# lpc11c14.net
KiCad netlist of a schematic drawn in Altium Designer
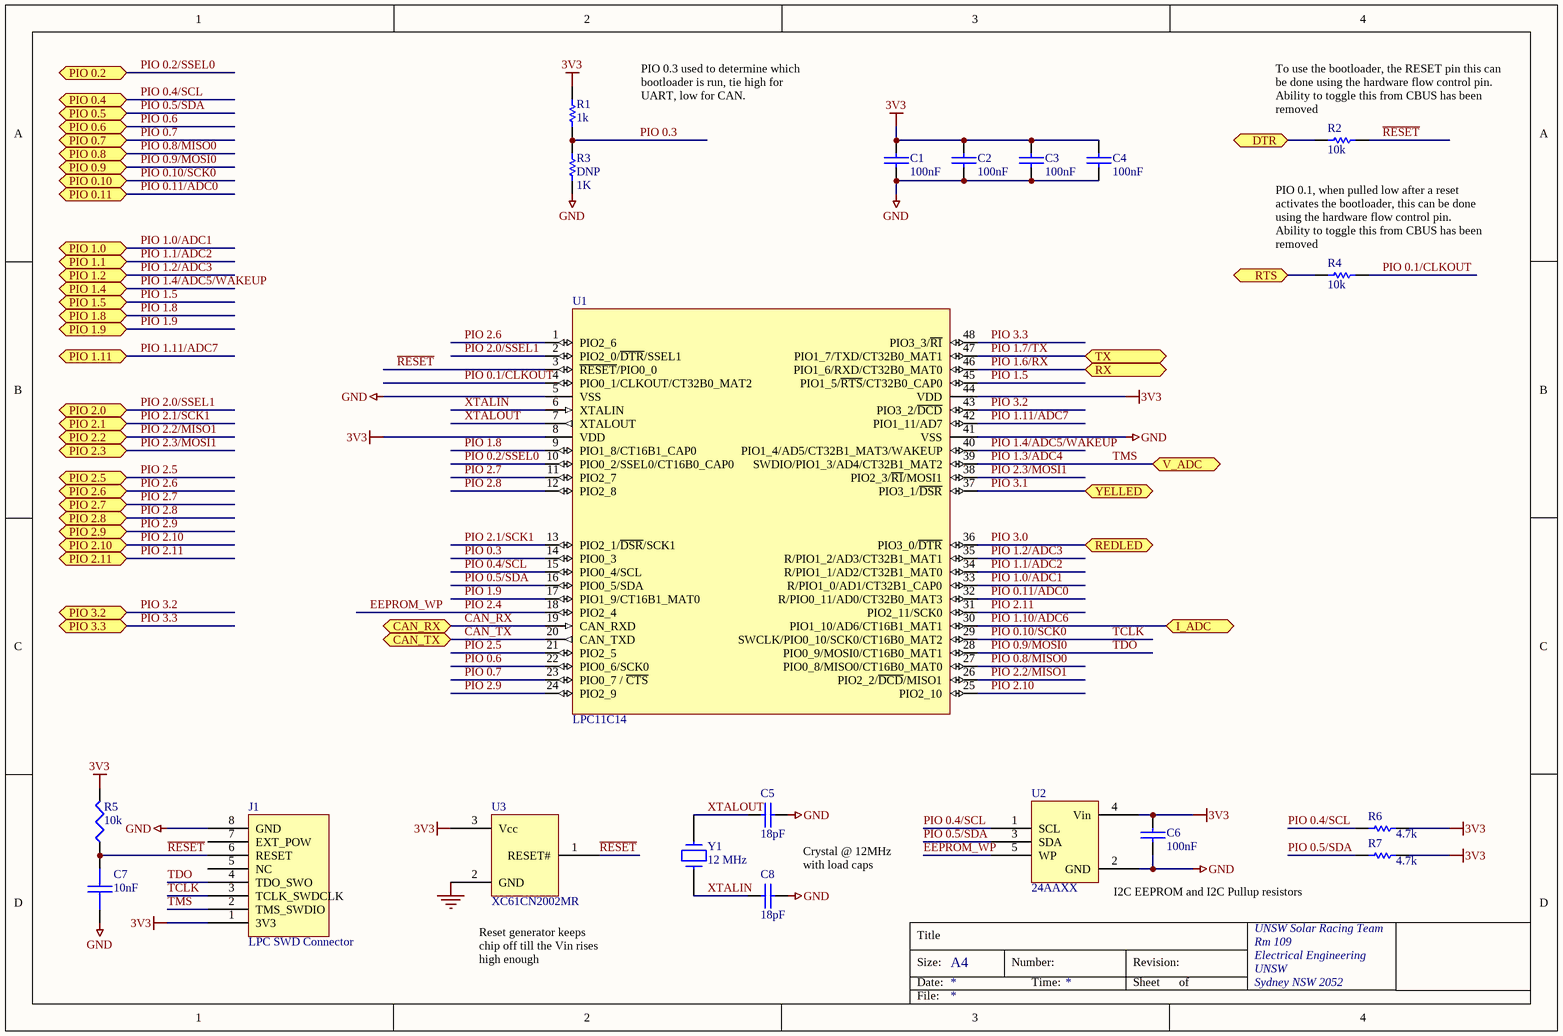
[diagram p0: lpc11c14.SchDoc]

(export (version "E")
  (design (tool "Eeschema 10.0.6"))
  (components
    (comp (ref "C1")
      (value "100nF")
      (footprint "0603")
      (description "Capacitor")
      (libsource (lib "*") (part "CAP"))
    )
    (comp (ref "C2")
      (value "100nF")
      (footprint "0603")
      (description "Capacitor")
      (libsource (lib "*") (part "CAP"))
    )
    (comp (ref "C3")
      (value "100nF")
      (footprint "0603")
      (description "Capacitor")
      (libsource (lib "*") (part "CAP"))
    )
    (comp (ref "C4")
      (value "100nF")
      (footprint "0603")
      (description "Capacitor")
      (libsource (lib "*") (part "CAP"))
    )
    (comp (ref "C5")
      (value "18pF")
      (footprint "0603")
      (description "Capacitor")
      (fields
        (field (name "MANUFACTURER") "Kemet")
        (field (name "MANUFACTURER PART NUMBER") "CBR06C180FAGAC")
      )
      (libsource (lib "*") (part "CAP"))
    )
    (comp (ref "C6")
      (value "100nF")
      (footprint "0603")
      (description "Capacitor")
      (libsource (lib "*") (part "CAP"))
    )
    (comp (ref "C7")
      (value "10nF")
      (footprint "0603")
      (description "Capacitor")
      (libsource (lib "SunswiftLib20030312RR") (part "CAP"))
    )
    (comp (ref "C8")
      (value "18pF")
      (footprint "0603")
      (description "Capacitor")
      (fields
        (field (name "MANUFACTURER") "Kemet")
        (field (name "MANUFACTURER PART NUMBER") "CBR06C180FAGAC")
      )
      (libsource (lib "*") (part "CAP"))
    )
    (comp (ref "J1")
      (value "LPC SWD Connector")
      (footprint "IDC8")
      (libsource (lib "2009_BatteryMaster") (part "LPCLink_Connector"))
    )
    (comp (ref "R1")
      (value "1k")
      (footprint "0603")
      (description "Semiconductor Resistor")
      (fields (field (name "PUBLISHER") "Altium Limited"))
      (libsource (lib "Miscellaneous Devices") (part "Res Semi"))
    )
    (comp (ref "R2")
      (value "10k")
      (footprint "0603")
      (description "Semiconductor Resistor")
      (fields (field (name "PUBLISHER") "Altium Limited"))
      (libsource (lib "Miscellaneous Devices") (part "Res Semi"))
    )
    (comp (ref "R3")
      (value "DNP")
      (footprint "0603")
      (description "Semiconductor Resistor")
      (fields (field (name "ALTIUM_VALUE") "1K") (field (name "PUBLISHER") "Altium Limited"))
      (libsource (lib "Miscellaneous Devices") (part "Res Semi"))
    )
    (comp (ref "R4")
      (value "10k")
      (footprint "0603")
      (description "Semiconductor Resistor")
      (fields (field (name "PUBLISHER") "Altium Limited"))
      (libsource (lib "Miscellaneous Devices") (part "Res Semi"))
    )
    (comp (ref "R5")
      (value "10k")
      (footprint "0603")
      (description "Resistor")
      (libsource (lib "SunswiftLib20030312RR") (part "RES1"))
    )
    (comp (ref "R6")
      (value "4.7k")
      (footprint "0603")
      (description "Semiconductor Resistor")
      (fields (field (name "PUBLISHER") "Altium Limited"))
      (libsource (lib "Miscellaneous Devices") (part "Res Semi"))
    )
    (comp (ref "R7")
      (value "4.7k")
      (footprint "0603")
      (description "Semiconductor Resistor")
      (fields (field (name "PUBLISHER") "Altium Limited"))
      (libsource (lib "Miscellaneous Devices") (part "Res Semi"))
    )
    (comp (ref "U1")
      (value "LPC11C14")
      (footprint "QFP48")
      (description "NXP LPC11C14 Microcontroller")
      (libsource (lib "LPC") (part "LPC11C14_Full"))
    )
    (comp (ref "U2")
      (value "24AAXX")
      (footprint "SOT23-5")
      (description "I2C EEPROM for SOT23-5 package")
      (libsource (lib "MiscellaneousIC") (part "24AAXX"))
    )
    (comp (ref "U3")
      (value "XC61CN2002MR")
      (footprint "SOT23-3")
      (description "SOT23 reset generator")
      (libsource (lib "*") (part "XC61F"))
    )
    (comp (ref "Y1")
      (value "12 MHz")
      (footprint "HC49/4H")
      (description "Crystal")
      (libsource (lib "*") (part "CRYSTAL"))
    )
  )
  (nets
    (net (code "1") (name "/CAN_RX") (class "Default")
      (node (ref "U1") (pin "19") (pinfunction "CAN_RXD_19") (pintype "input"))
    )
    (net (code "2") (name "/CAN_TX") (class "Default")
      (node (ref "U1") (pin "20") (pinfunction "CAN_TXD_20") (pintype "output"))
    )
    (net (code "3") (name "/DTR") (class "Default")
      (node (ref "R2") (pin "1") (pinfunction "1_1") (pintype "passive"))
    )
    (net (code "4") (name "/EEPROM_WP") (class "Default")
      (node (ref "U1") (pin "18") (pinfunction "PIO2_4_18") (pintype "bidirectional"))
      (node (ref "U2") (pin "5") (pinfunction "WP_5") (pintype "passive"))
    )
    (net (code "5") (name "/PIO 0.1{slash}CLKOUT") (class "Default")
      (node (ref "R4") (pin "2") (pinfunction "2_2") (pintype "passive"))
      (node (ref "U1") (pin "4") (pinfunction "PIO0_1/CLKOUT/CT32B0_MAT2_4") (pintype "bidirectional"))
    )
    (net (code "6") (name "/PIO 0.2{slash}SSEL0") (class "Default")
      (node (ref "U1") (pin "10") (pinfunction "PIO0_2/SSEL0/CT16B0_CAP0_10") (pintype "bidirectional"))
    )
    (net (code "7") (name "/PIO 0.3") (class "Default")
      (node (ref "R1") (pin "1") (pinfunction "1_1") (pintype "passive"))
      (node (ref "R3") (pin "2") (pinfunction "2_2") (pintype "passive"))
      (node (ref "U1") (pin "14") (pinfunction "PIO0_3_14") (pintype "bidirectional"))
    )
    (net (code "8") (name "/PIO 0.4{slash}SCL") (class "Default")
      (node (ref "R6") (pin "1") (pinfunction "1_1") (pintype "passive"))
      (node (ref "U1") (pin "15") (pinfunction "PIO0_4/SCL_15") (pintype "bidirectional"))
      (node (ref "U2") (pin "1") (pinfunction "SCL_1") (pintype "passive"))
    )
    (net (code "9") (name "/PIO 0.5{slash}SDA") (class "Default")
      (node (ref "R7") (pin "1") (pinfunction "1_1") (pintype "passive"))
      (node (ref "U1") (pin "16") (pinfunction "PIO0_5/SDA_16") (pintype "bidirectional"))
      (node (ref "U2") (pin "3") (pinfunction "SDA_3") (pintype "passive"))
    )
    (net (code "10") (name "/PIO 0.6") (class "Default")
      (node (ref "U1") (pin "22") (pinfunction "PIO0_6/SCK0_22") (pintype "bidirectional"))
    )
    (net (code "11") (name "/PIO 0.7") (class "Default")
      (node (ref "U1") (pin "23") (pinfunction "PIO0_7_/_~{CTS}_23") (pintype "bidirectional"))
    )
    (net (code "12") (name "/PIO 0.8{slash}MISO0") (class "Default")
      (node (ref "U1") (pin "27") (pinfunction "PIO0_8/MISO0/CT16B0_MAT0_27") (pintype "bidirectional"))
    )
    (net (code "13") (name "/PIO 0.9{slash}MOSI0") (class "Default")
      (node (ref "J1") (pin "4") (pinfunction "TDO_SWO_4") (pintype "passive"))
      (node (ref "U1") (pin "28") (pinfunction "PIO0_9/MOSI0/CT16B0_MAT1_28") (pintype "bidirectional"))
    )
    (net (code "14") (name "/PIO 0.10{slash}SCK0") (class "Default")
      (node (ref "J1") (pin "3") (pinfunction "TCLK_SWDCLK_3") (pintype "passive"))
      (node (ref "U1") (pin "29") (pinfunction "SWCLK/PIO0_10/SCK0/CT16B0_MAT2_29") (pintype "bidirectional"))
    )
    (net (code "15") (name "/PIO 0.11{slash}ADC0") (class "Default")
      (node (ref "U1") (pin "32") (pinfunction "R/PIO0_11/AD0/CT32B0_MAT3_32") (pintype "bidirectional"))
    )
    (net (code "16") (name "/PIO 1.0{slash}ADC1") (class "Default")
      (node (ref "U1") (pin "33") (pinfunction "R/PIO1_0/AD1/CT32B1_CAP0_33") (pintype "bidirectional"))
    )
    (net (code "17") (name "/PIO 1.1{slash}ADC2") (class "Default")
      (node (ref "U1") (pin "34") (pinfunction "R/PIO1_1/AD2/CT32B1_MAT0_34") (pintype "bidirectional"))
    )
    (net (code "18") (name "/PIO 1.2{slash}ADC3") (class "Default")
      (node (ref "U1") (pin "35") (pinfunction "R/PIO1_2/AD3/CT32B1_MAT1_35") (pintype "bidirectional"))
    )
    (net (code "19") (name "/PIO 1.3{slash}ADC4") (class "Default")
      (node (ref "J1") (pin "2") (pinfunction "TMS_SWDIO_2") (pintype "passive"))
      (node (ref "U1") (pin "39") (pinfunction "SWDIO/PIO1_3/AD4/CT32B1_MAT2_39") (pintype "bidirectional"))
    )
    (net (code "20") (name "/PIO 1.4{slash}ADC5{slash}WAKEUP") (class "Default")
      (node (ref "U1") (pin "40") (pinfunction "PIO1_4/AD5/CT32B1_MAT3/WAKEUP_40") (pintype "bidirectional"))
    )
    (net (code "21") (name "/PIO 1.5") (class "Default")
      (node (ref "U1") (pin "45") (pinfunction "PIO1_5/~{RTS}/CT32B0_CAP0_45") (pintype "bidirectional"))
    )
    (net (code "22") (name "/PIO 1.6{slash}RX") (class "Default")
      (node (ref "U1") (pin "46") (pinfunction "PIO1_6/RXD/CT32B0_MAT0_46") (pintype "bidirectional"))
    )
    (net (code "23") (name "/PIO 1.7{slash}TX") (class "Default")
      (node (ref "U1") (pin "47") (pinfunction "PIO1_7/TXD/CT32B0_MAT1_47") (pintype "bidirectional"))
    )
    (net (code "24") (name "/PIO 1.8") (class "Default")
      (node (ref "U1") (pin "9") (pinfunction "PIO1_8/CT16B1_CAP0_9") (pintype "bidirectional"))
    )
    (net (code "25") (name "/PIO 1.9") (class "Default")
      (node (ref "U1") (pin "17") (pinfunction "PIO1_9/CT16B1_MAT0_17") (pintype "bidirectional"))
    )
    (net (code "26") (name "/PIO 1.10{slash}ADC6") (class "Default")
      (node (ref "U1") (pin "30") (pinfunction "PIO1_10/AD6/CT16B1_MAT1_30") (pintype "bidirectional"))
    )
    (net (code "27") (name "/PIO 1.11{slash}ADC7") (class "Default")
      (node (ref "U1") (pin "42") (pinfunction "PIO1_11/AD7_42") (pintype "bidirectional"))
    )
    (net (code "28") (name "/PIO 2.0{slash}SSEL1") (class "Default")
      (node (ref "U1") (pin "2") (pinfunction "PIO2_0/~{DTR}/SSEL1_2") (pintype "bidirectional"))
    )
    (net (code "29") (name "/PIO 2.1{slash}SCK1") (class "Default")
      (node (ref "U1") (pin "13") (pinfunction "PIO2_1/~{DSR}/SCK1_13") (pintype "bidirectional"))
    )
    (net (code "30") (name "/PIO 2.2{slash}MISO1") (class "Default")
      (node (ref "U1") (pin "26") (pinfunction "PIO2_2/~{DCD}/MISO1_26") (pintype "bidirectional"))
    )
    (net (code "31") (name "/PIO 2.3{slash}MOSI1") (class "Default")
      (node (ref "U1") (pin "38") (pinfunction "PIO2_3/~{RI}/MOSI1_38") (pintype "bidirectional"))
    )
    (net (code "32") (name "/PIO 2.5") (class "Default")
      (node (ref "U1") (pin "21") (pinfunction "PIO2_5_21") (pintype "bidirectional"))
    )
    (net (code "33") (name "/PIO 2.6") (class "Default")
      (node (ref "U1") (pin "1") (pinfunction "PIO2_6_1") (pintype "bidirectional"))
    )
    (net (code "34") (name "/PIO 2.7") (class "Default")
      (node (ref "U1") (pin "11") (pinfunction "PIO2_7_11") (pintype "bidirectional"))
    )
    (net (code "35") (name "/PIO 2.8") (class "Default")
      (node (ref "U1") (pin "12") (pinfunction "PIO2_8_12") (pintype "bidirectional"))
    )
    (net (code "36") (name "/PIO 2.9") (class "Default")
      (node (ref "U1") (pin "24") (pinfunction "PIO2_9_24") (pintype "bidirectional"))
    )
    (net (code "37") (name "/PIO 2.10") (class "Default")
      (node (ref "U1") (pin "25") (pinfunction "PIO2_10_25") (pintype "bidirectional"))
    )
    (net (code "38") (name "/PIO 2.11") (class "Default")
      (node (ref "U1") (pin "31") (pinfunction "PIO2_11/SCK0_31") (pintype "bidirectional"))
    )
    (net (code "39") (name "/PIO 3.0") (class "Default")
      (node (ref "U1") (pin "36") (pinfunction "PIO3_0/~{DTR}_36") (pintype "bidirectional"))
    )
    (net (code "40") (name "/PIO 3.1") (class "Default")
      (node (ref "U1") (pin "37") (pinfunction "PIO3_1/~{DSR}_37") (pintype "bidirectional"))
    )
    (net (code "41") (name "/PIO 3.2") (class "Default")
      (node (ref "U1") (pin "43") (pinfunction "PIO3_2/~{DCD}_43") (pintype "bidirectional"))
    )
    (net (code "42") (name "/PIO 3.3") (class "Default")
      (node (ref "U1") (pin "48") (pinfunction "PIO3_3/~{RI}_48") (pintype "bidirectional"))
    )
    (net (code "43") (name "/RTS") (class "Default")
      (node (ref "R4") (pin "1") (pinfunction "1_1") (pintype "passive"))
    )
    (net (code "44") (name "/XTALIN") (class "Default")
      (node (ref "C8") (pin "1") (pinfunction "1_1") (pintype "passive"))
      (node (ref "U1") (pin "6") (pinfunction "XTALIN_6") (pintype "input"))
      (node (ref "Y1") (pin "1") (pinfunction "1_1") (pintype "passive"))
    )
    (net (code "45") (name "/XTALOUT") (class "Default")
      (node (ref "C5") (pin "1") (pinfunction "1_1") (pintype "passive"))
      (node (ref "U1") (pin "7") (pinfunction "XTALOUT_7") (pintype "output"))
      (node (ref "Y1") (pin "2") (pinfunction "2_2") (pintype "passive"))
    )
    (net (code "46") (name "/~{RESET}") (class "Default")
      (node (ref "C7") (pin "1") (pinfunction "1_1") (pintype "passive"))
      (node (ref "J1") (pin "6") (pinfunction "RESET_6") (pintype "passive"))
      (node (ref "R2") (pin "2") (pinfunction "2_2") (pintype "passive"))
      (node (ref "R5") (pin "1") (pinfunction "1_1") (pintype "passive"))
      (node (ref "U1") (pin "3") (pinfunction "~{RESET}/PIO0_0_3") (pintype "bidirectional"))
      (node (ref "U3") (pin "1") (pinfunction "RESET#_1") (pintype "passive"))
    )
    (net (code "47") (name "3V3") (class "Default")
      (node (ref "C1") (pin "1") (pinfunction "1_1") (pintype "passive"))
      (node (ref "C2") (pin "1") (pinfunction "1_1") (pintype "passive"))
      (node (ref "C3") (pin "1") (pinfunction "1_1") (pintype "passive"))
      (node (ref "C4") (pin "1") (pinfunction "1_1") (pintype "passive"))
      (node (ref "C6") (pin "1") (pinfunction "1_1") (pintype "passive"))
      (node (ref "J1") (pin "1") (pinfunction "3V3_1") (pintype "passive"))
      (node (ref "R1") (pin "2") (pinfunction "2_2") (pintype "passive"))
      (node (ref "R5") (pin "2") (pinfunction "2_2") (pintype "passive"))
      (node (ref "R6") (pin "2") (pinfunction "2_2") (pintype "passive"))
      (node (ref "R7") (pin "2") (pinfunction "2_2") (pintype "passive"))
      (node (ref "U1") (pin "44") (pinfunction "VDD_44") (pintype "power_in"))
      (node (ref "U1") (pin "8") (pinfunction "VDD_8") (pintype "power_in"))
      (node (ref "U2") (pin "4") (pinfunction "Vin_4") (pintype "passive"))
      (node (ref "U3") (pin "3") (pinfunction "Vcc_3") (pintype "passive"))
    )
    (net (code "48") (name "GND") (class "Default")
      (node (ref "C1") (pin "2") (pinfunction "2_2") (pintype "passive"))
      (node (ref "C2") (pin "2") (pinfunction "2_2") (pintype "passive"))
      (node (ref "C3") (pin "2") (pinfunction "2_2") (pintype "passive"))
      (node (ref "C4") (pin "2") (pinfunction "2_2") (pintype "passive"))
      (node (ref "C5") (pin "2") (pinfunction "2_2") (pintype "passive"))
      (node (ref "C6") (pin "2") (pinfunction "2_2") (pintype "passive"))
      (node (ref "C7") (pin "2") (pinfunction "2_2") (pintype "passive"))
      (node (ref "C8") (pin "2") (pinfunction "2_2") (pintype "passive"))
      (node (ref "J1") (pin "8") (pinfunction "GND_8") (pintype "passive"))
      (node (ref "R3") (pin "1") (pinfunction "1_1") (pintype "passive"))
      (node (ref "U1") (pin "41") (pinfunction "VSS_41") (pintype "power_in"))
      (node (ref "U1") (pin "5") (pinfunction "VSS_5") (pintype "power_in"))
      (node (ref "U2") (pin "2") (pinfunction "GND_2") (pintype "passive"))
      (node (ref "U3") (pin "2") (pinfunction "GND_2") (pintype "passive"))
    )
    (net (code "49") (name "unconnected-(J1-EXT_POW-Pad7)") (class "Default")
      (node (ref "J1") (pin "7") (pinfunction "EXT_POW_7") (pintype "passive"))
    )
    (net (code "50") (name "unconnected-(J1-NC-Pad5)") (class "Default")
      (node (ref "J1") (pin "5") (pinfunction "NC_5") (pintype "passive"))
    )
  )
)
